# 130817_AriloRX_0_0.net
KiCad netlist of a schematic drawn in EAGLE
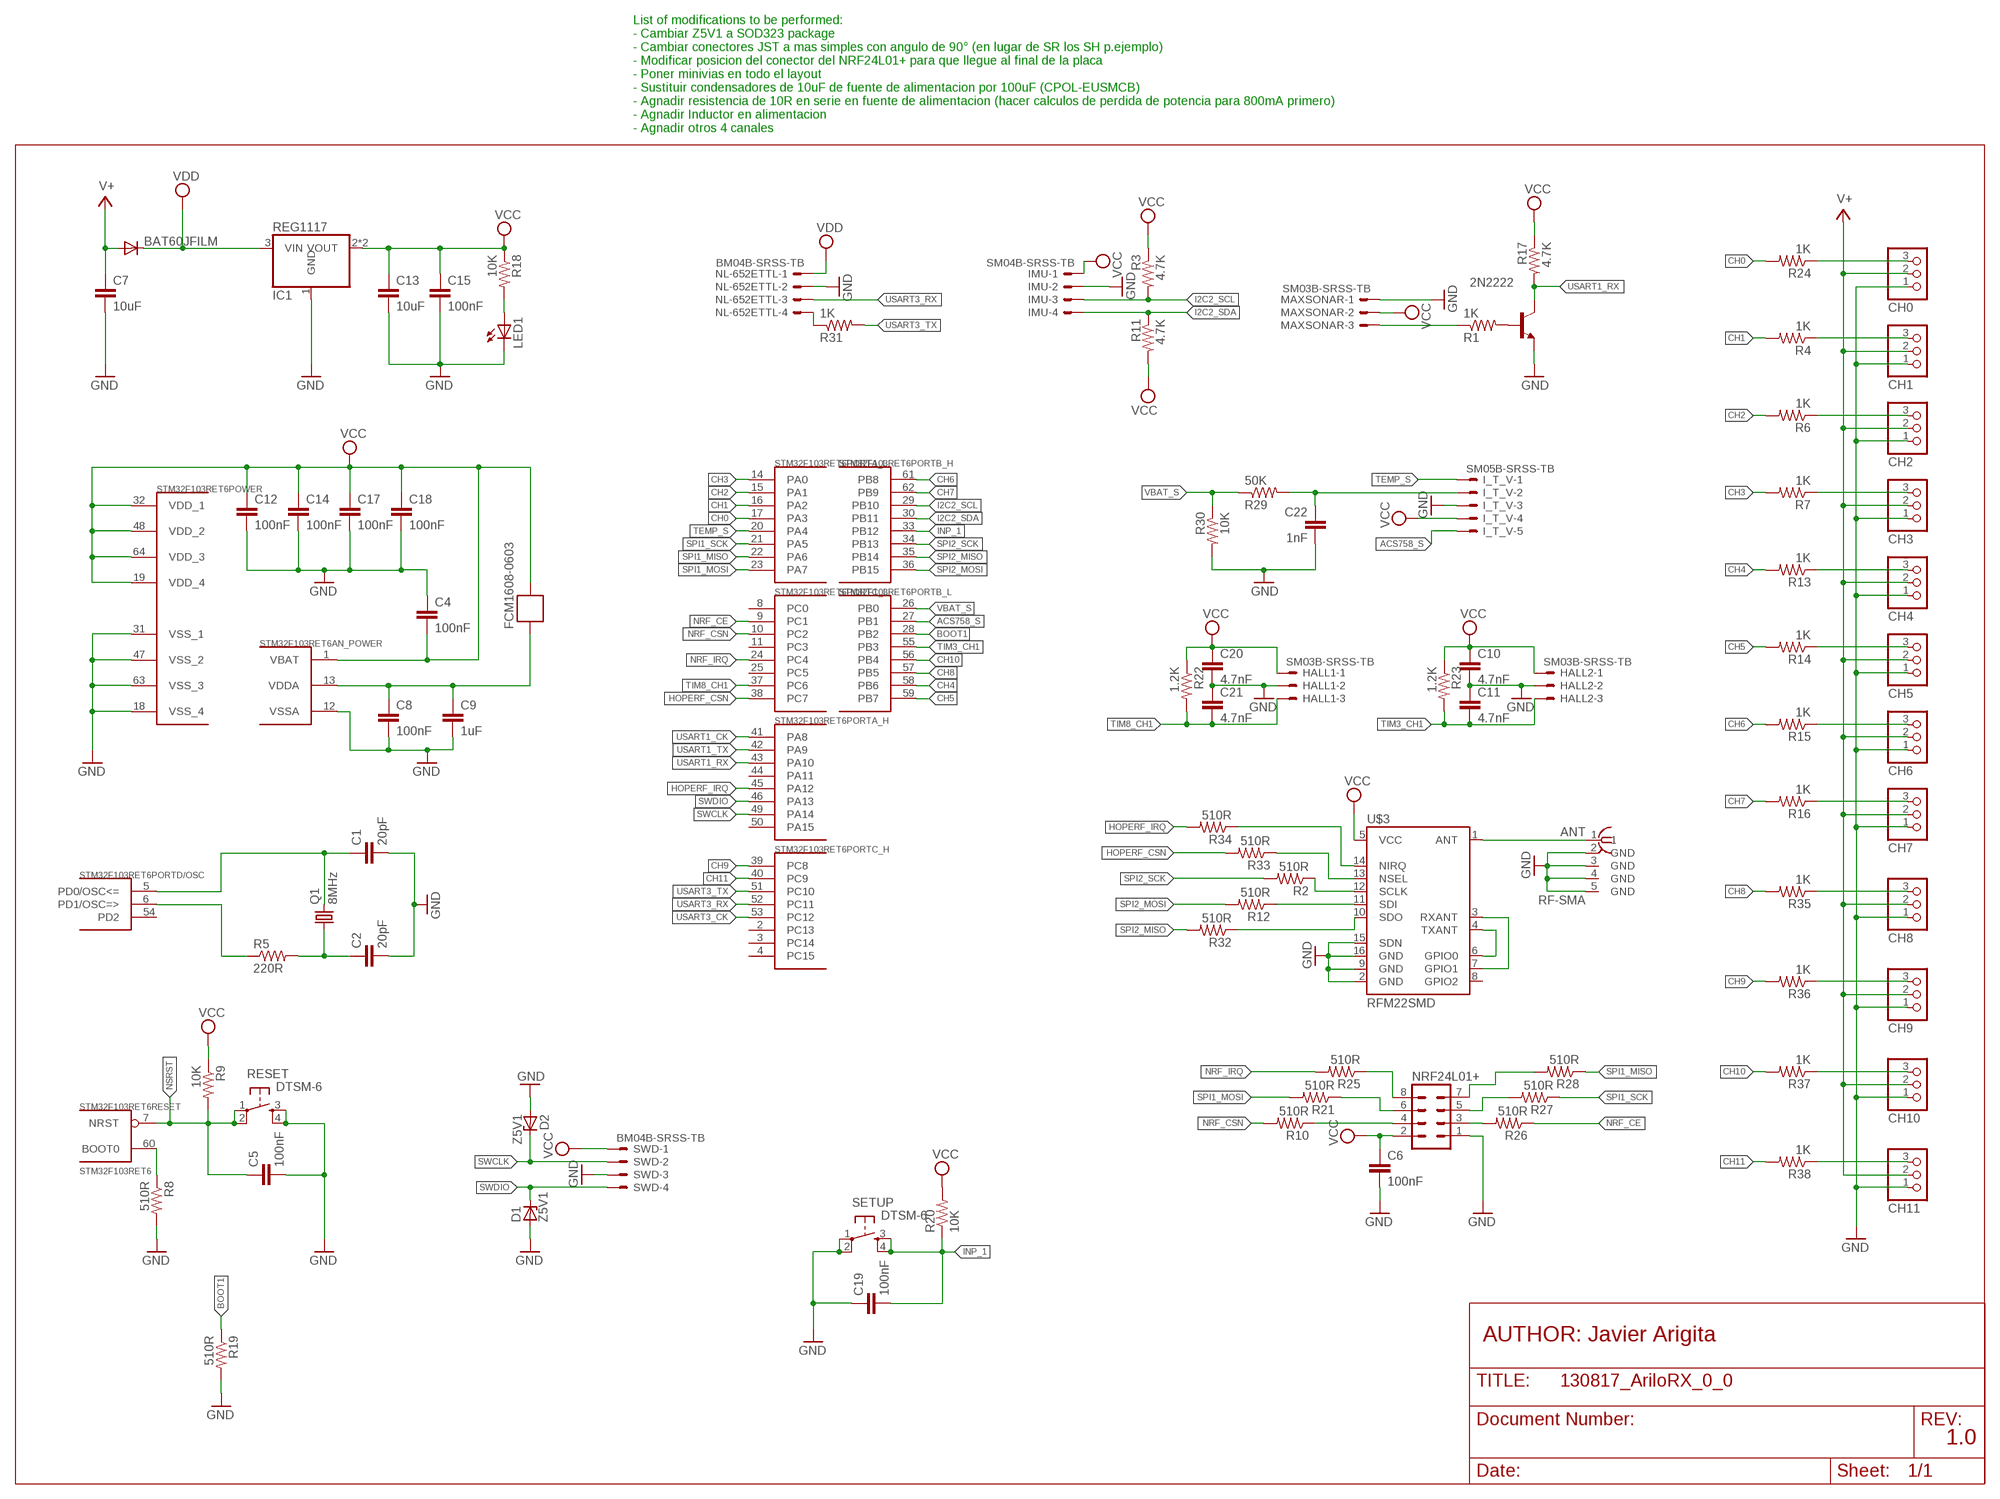
[diagram p0: schematic, sheet 1]

(export (version "E")
  (design (tool "Eeschema 10.0.6"))
  (components
    (comp (ref "2N2222")
      (value "MMBT2222ALT1-NPN-SOT23-BEC")
      (footprint "eagle-import:SOT23-BEC")
      (libsource (lib "eagle-import") (part "-NPN-SOT23-BECMMBT2222ALT1"))
    )
    (comp (ref "ANT")
      (value "RF-SMA")
      (footprint "eagle-import:BU-SMA-H")
      (libsource (lib "eagle-import") (part "RF-SMA"))
    )
    (comp (ref "BAT60JFILM")
      (value "DIODE-SOD323-R")
      (footprint "eagle-import:SOD323-R")
      (libsource (lib "eagle-import") (part "DIODE-SOD323-R"))
    )
    (comp (ref "C1")
      (value "20pF")
      (footprint "eagle-import:C0805")
      (libsource (lib "eagle-import") (part "C-EUC0805"))
    )
    (comp (ref "C2")
      (value "20pF")
      (footprint "eagle-import:C0805")
      (libsource (lib "eagle-import") (part "C-EUC0805"))
    )
    (comp (ref "C4")
      (value "100nF")
      (footprint "eagle-import:C0805")
      (libsource (lib "eagle-import") (part "C-EUC0805"))
    )
    (comp (ref "C5")
      (value "100nF")
      (footprint "eagle-import:C0805")
      (libsource (lib "eagle-import") (part "C-EUC0805"))
    )
    (comp (ref "C6")
      (value "100nF")
      (footprint "eagle-import:C0805")
      (libsource (lib "eagle-import") (part "C-EUC0805"))
    )
    (comp (ref "C7")
      (value "10uF")
      (footprint "eagle-import:C3216")
      (libsource (lib "eagle-import") (part "resistor_C-EUC3216"))
    )
    (comp (ref "C8")
      (value "100nF")
      (footprint "eagle-import:C0805")
      (libsource (lib "eagle-import") (part "C-EUC0805"))
    )
    (comp (ref "C9")
      (value "1uF")
      (footprint "eagle-import:C3216")
      (libsource (lib "eagle-import") (part "resistor_C-EUC3216"))
    )
    (comp (ref "C10")
      (value "4.7nF")
      (footprint "eagle-import:C0805")
      (libsource (lib "eagle-import") (part "C-EUC0805"))
    )
    (comp (ref "C11")
      (value "4.7nF")
      (footprint "eagle-import:C0805")
      (libsource (lib "eagle-import") (part "C-EUC0805"))
    )
    (comp (ref "C12")
      (value "100nF")
      (footprint "eagle-import:C0805")
      (libsource (lib "eagle-import") (part "C-EUC0805"))
    )
    (comp (ref "C13")
      (value "10uF")
      (footprint "eagle-import:C3216")
      (libsource (lib "eagle-import") (part "resistor_C-EUC3216"))
    )
    (comp (ref "C14")
      (value "100nF")
      (footprint "eagle-import:C0805")
      (libsource (lib "eagle-import") (part "C-EUC0805"))
    )
    (comp (ref "C15")
      (value "100nF")
      (footprint "eagle-import:C0805")
      (libsource (lib "eagle-import") (part "C-EUC0805"))
    )
    (comp (ref "C17")
      (value "100nF")
      (footprint "eagle-import:C0805")
      (libsource (lib "eagle-import") (part "C-EUC0805"))
    )
    (comp (ref "C18")
      (value "100nF")
      (footprint "eagle-import:C0805")
      (libsource (lib "eagle-import") (part "C-EUC0805"))
    )
    (comp (ref "C19")
      (value "100nF")
      (footprint "eagle-import:C0805")
      (libsource (lib "eagle-import") (part "C-EUC0805"))
    )
    (comp (ref "C20")
      (value "4.7nF")
      (footprint "eagle-import:C0805")
      (libsource (lib "eagle-import") (part "C-EUC0805"))
    )
    (comp (ref "C21")
      (value "4.7nF")
      (footprint "eagle-import:C0805")
      (libsource (lib "eagle-import") (part "C-EUC0805"))
    )
    (comp (ref "C22")
      (value "1nF")
      (footprint "eagle-import:C0805")
      (libsource (lib "eagle-import") (part "C-EUC0805"))
    )
    (comp (ref "CH0")
      (value "PINHD-1X3")
      (footprint "eagle-import:1X03")
      (libsource (lib "eagle-import") (part "PINHD-1X3"))
    )
    (comp (ref "CH1")
      (value "PINHD-1X3")
      (footprint "eagle-import:1X03")
      (libsource (lib "eagle-import") (part "PINHD-1X3"))
    )
    (comp (ref "CH2")
      (value "PINHD-1X3")
      (footprint "eagle-import:1X03")
      (libsource (lib "eagle-import") (part "PINHD-1X3"))
    )
    (comp (ref "CH3")
      (value "PINHD-1X3")
      (footprint "eagle-import:1X03")
      (libsource (lib "eagle-import") (part "PINHD-1X3"))
    )
    (comp (ref "CH4")
      (value "PINHD-1X3")
      (footprint "eagle-import:1X03")
      (libsource (lib "eagle-import") (part "PINHD-1X3"))
    )
    (comp (ref "CH5")
      (value "PINHD-1X3")
      (footprint "eagle-import:1X03")
      (libsource (lib "eagle-import") (part "PINHD-1X3"))
    )
    (comp (ref "CH6")
      (value "PINHD-1X3")
      (footprint "eagle-import:1X03")
      (libsource (lib "eagle-import") (part "PINHD-1X3"))
    )
    (comp (ref "CH7")
      (value "PINHD-1X3")
      (footprint "eagle-import:1X03")
      (libsource (lib "eagle-import") (part "PINHD-1X3"))
    )
    (comp (ref "CH8")
      (value "PINHD-1X3")
      (footprint "eagle-import:1X03")
      (libsource (lib "eagle-import") (part "PINHD-1X3"))
    )
    (comp (ref "CH9")
      (value "PINHD-1X3")
      (footprint "eagle-import:1X03")
      (libsource (lib "eagle-import") (part "PINHD-1X3"))
    )
    (comp (ref "CH10")
      (value "PINHD-1X3")
      (footprint "eagle-import:1X03")
      (libsource (lib "eagle-import") (part "PINHD-1X3"))
    )
    (comp (ref "CH11")
      (value "PINHD-1X3")
      (footprint "eagle-import:1X03")
      (libsource (lib "eagle-import") (part "PINHD-1X3"))
    )
    (comp (ref "D1")
      (value "Z5V1")
      (footprint "eagle-import:SOD80C")
      (libsource (lib "eagle-import") (part "ZENER-DIODESOD80C"))
    )
    (comp (ref "D2")
      (value "Z5V1")
      (footprint "eagle-import:SOD80C")
      (libsource (lib "eagle-import") (part "ZENER-DIODESOD80C"))
    )
    (comp (ref "FCM1608-0603")
      (value "FERRITE-BEAD")
      (footprint "eagle-import:R0603")
      (libsource (lib "eagle-import") (part "FERRITE-BEAD"))
    )
    (comp (ref "HALL1")
      (value "SM03B-SRSS-TB")
      (footprint "eagle-import:SM03B-SRSS-TB")
      (libsource (lib "eagle-import") (part "?M03B-SRSS-TBS"))
    )
    (comp (ref "HALL2")
      (value "SM03B-SRSS-TB")
      (footprint "eagle-import:SM03B-SRSS-TB")
      (libsource (lib "eagle-import") (part "?M03B-SRSS-TBS"))
    )
    (comp (ref "IC1")
      (value "REG1117")
      (footprint "eagle-import:SOT223")
      (libsource (lib "eagle-import") (part "REG1117"))
    )
    (comp (ref "IMU")
      (value "SM04B-SRSS-TB")
      (footprint "eagle-import:SM04B-SRSS-TB")
      (libsource (lib "eagle-import") (part "?M04B-SRSS-TBS"))
    )
    (comp (ref "I_T_V")
      (value "SM05B-SRSS-TB")
      (footprint "eagle-import:SM05B-SRSS-TB")
      (libsource (lib "eagle-import") (part "?M05B-SRSS-TBS"))
    )
    (comp (ref "LED1")
      (value "LED0805")
      (footprint "eagle-import:CHIPLED_0805")
      (libsource (lib "eagle-import") (part "LED0805"))
    )
    (comp (ref "MAXSONAR")
      (value "SM03B-SRSS-TB")
      (footprint "eagle-import:SM03B-SRSS-TB")
      (libsource (lib "eagle-import") (part "?M03B-SRSS-TBS"))
    )
    (comp (ref "NL-652ETTL")
      (value "BM04B-SRSS-TB")
      (footprint "eagle-import:BM04B-SRSS-TB")
      (libsource (lib "eagle-import") (part "?M04B-SRSS-TBB"))
    )
    (comp (ref "NRF24L01+")
      (value "MA04-2")
      (footprint "eagle-import:MA04-2")
      (libsource (lib "eagle-import") (part "MA04-2"))
    )
    (comp (ref "Q1")
      (value "8MHz")
      (footprint "eagle-import:SM49")
      (libsource (lib "eagle-import") (part "CRYSTALSM49"))
    )
    (comp (ref "R1")
      (value "1K")
      (footprint "eagle-import:R0805")
      (libsource (lib "eagle-import") (part "RESISTOR0805"))
    )
    (comp (ref "R2")
      (value "510R")
      (footprint "eagle-import:R0805")
      (libsource (lib "eagle-import") (part "RESISTOR0805"))
    )
    (comp (ref "R3")
      (value "4.7K")
      (footprint "eagle-import:R0805")
      (libsource (lib "eagle-import") (part "RESISTOR0805"))
    )
    (comp (ref "R4")
      (value "1K")
      (footprint "eagle-import:R0805")
      (libsource (lib "eagle-import") (part "RESISTOR0805"))
    )
    (comp (ref "R5")
      (value "220R")
      (footprint "eagle-import:R0805")
      (libsource (lib "eagle-import") (part "RESISTOR0805"))
    )
    (comp (ref "R6")
      (value "1K")
      (footprint "eagle-import:R0805")
      (libsource (lib "eagle-import") (part "RESISTOR0805"))
    )
    (comp (ref "R7")
      (value "1K")
      (footprint "eagle-import:R0805")
      (libsource (lib "eagle-import") (part "RESISTOR0805"))
    )
    (comp (ref "R8")
      (value "510R")
      (footprint "eagle-import:R0805")
      (libsource (lib "eagle-import") (part "RESISTOR0805"))
    )
    (comp (ref "R9")
      (value "10K")
      (footprint "eagle-import:R0805")
      (libsource (lib "eagle-import") (part "RESISTOR0805"))
    )
    (comp (ref "R10")
      (value "510R")
      (footprint "eagle-import:R0805")
      (libsource (lib "eagle-import") (part "RESISTOR0805"))
    )
    (comp (ref "R11")
      (value "4.7K")
      (footprint "eagle-import:R0805")
      (libsource (lib "eagle-import") (part "RESISTOR0805"))
    )
    (comp (ref "R12")
      (value "510R")
      (footprint "eagle-import:R0805")
      (libsource (lib "eagle-import") (part "RESISTOR0805"))
    )
    (comp (ref "R13")
      (value "1K")
      (footprint "eagle-import:R0805")
      (libsource (lib "eagle-import") (part "RESISTOR0805"))
    )
    (comp (ref "R14")
      (value "1K")
      (footprint "eagle-import:R0805")
      (libsource (lib "eagle-import") (part "RESISTOR0805"))
    )
    (comp (ref "R15")
      (value "1K")
      (footprint "eagle-import:R0805")
      (libsource (lib "eagle-import") (part "RESISTOR0805"))
    )
    (comp (ref "R16")
      (value "1K")
      (footprint "eagle-import:R0805")
      (libsource (lib "eagle-import") (part "RESISTOR0805"))
    )
    (comp (ref "R17")
      (value "4.7K")
      (footprint "eagle-import:R0805")
      (libsource (lib "eagle-import") (part "RESISTOR0805"))
    )
    (comp (ref "R18")
      (value "10K")
      (footprint "eagle-import:R0805")
      (libsource (lib "eagle-import") (part "RESISTOR0805"))
    )
    (comp (ref "R19")
      (value "510R")
      (footprint "eagle-import:R0805")
      (libsource (lib "eagle-import") (part "RESISTOR0805"))
    )
    (comp (ref "R20")
      (value "10K")
      (footprint "eagle-import:R0805")
      (libsource (lib "eagle-import") (part "RESISTOR0805"))
    )
    (comp (ref "R21")
      (value "510R")
      (footprint "eagle-import:R0805")
      (libsource (lib "eagle-import") (part "RESISTOR0805"))
    )
    (comp (ref "R22")
      (value "1.2K")
      (footprint "eagle-import:R0805")
      (libsource (lib "eagle-import") (part "RESISTOR0805"))
    )
    (comp (ref "R23")
      (value "1.2K")
      (footprint "eagle-import:R0805")
      (libsource (lib "eagle-import") (part "RESISTOR0805"))
    )
    (comp (ref "R24")
      (value "1K")
      (footprint "eagle-import:R0805")
      (libsource (lib "eagle-import") (part "RESISTOR0805"))
    )
    (comp (ref "R25")
      (value "510R")
      (footprint "eagle-import:R0805")
      (libsource (lib "eagle-import") (part "RESISTOR0805"))
    )
    (comp (ref "R26")
      (value "510R")
      (footprint "eagle-import:R0805")
      (libsource (lib "eagle-import") (part "RESISTOR0805"))
    )
    (comp (ref "R27")
      (value "510R")
      (footprint "eagle-import:R0805")
      (libsource (lib "eagle-import") (part "RESISTOR0805"))
    )
    (comp (ref "R28")
      (value "510R")
      (footprint "eagle-import:R0805")
      (libsource (lib "eagle-import") (part "RESISTOR0805"))
    )
    (comp (ref "R29")
      (value "50K")
      (footprint "eagle-import:R0805")
      (libsource (lib "eagle-import") (part "RESISTOR0805"))
    )
    (comp (ref "R30")
      (value "10K")
      (footprint "eagle-import:R0805")
      (libsource (lib "eagle-import") (part "RESISTOR0805"))
    )
    (comp (ref "R31")
      (value "1K")
      (footprint "eagle-import:R0805")
      (libsource (lib "eagle-import") (part "RESISTOR0805"))
    )
    (comp (ref "R32")
      (value "510R")
      (footprint "eagle-import:R0805")
      (libsource (lib "eagle-import") (part "RESISTOR0805"))
    )
    (comp (ref "R33")
      (value "510R")
      (footprint "eagle-import:R0805")
      (libsource (lib "eagle-import") (part "RESISTOR0805"))
    )
    (comp (ref "R34")
      (value "510R")
      (footprint "eagle-import:R0805")
      (libsource (lib "eagle-import") (part "RESISTOR0805"))
    )
    (comp (ref "R35")
      (value "1K")
      (footprint "eagle-import:R0805")
      (libsource (lib "eagle-import") (part "RESISTOR0805"))
    )
    (comp (ref "R36")
      (value "1K")
      (footprint "eagle-import:R0805")
      (libsource (lib "eagle-import") (part "RESISTOR0805"))
    )
    (comp (ref "R37")
      (value "1K")
      (footprint "eagle-import:R0805")
      (libsource (lib "eagle-import") (part "RESISTOR0805"))
    )
    (comp (ref "R38")
      (value "1K")
      (footprint "eagle-import:R0805")
      (libsource (lib "eagle-import") (part "RESISTOR0805"))
    )
    (comp (ref "RESET")
      (value "DTSM-6")
      (footprint "eagle-import:DTSM-6")
      (libsource (lib "eagle-import") (part "DTSM-6"))
    )
    (comp (ref "SETUP")
      (value "DTSM-6")
      (footprint "eagle-import:DTSM-6")
      (libsource (lib "eagle-import") (part "DTSM-6"))
    )
    (comp (ref "STM32F103RET6")
      (value "STM32F103RET6")
      (footprint "eagle-import:TQFP64")
      (libsource (lib "eagle-import") (part "STM32F10XRXT6"))
    )
    (comp (ref "SWD")
      (value "BM04B-SRSS-TB")
      (footprint "eagle-import:BM04B-SRSS-TB")
      (libsource (lib "eagle-import") (part "?M04B-SRSS-TBB"))
    )
    (comp (ref "U$3")
      (value "RFM22SMD")
      (footprint "eagle-import:RFM22-XXX-S2")
      (libsource (lib "eagle-import") (part "RFM22SMD"))
    )
  )
  (nets
    (net (code "1") (name "ACS758_S") (class "Default")
      (node (ref "I_T_V") (pin "5") (pinfunction "S_5") (pintype "passive"))
      (node (ref "STM32F103RET6") (pin "27") (pinfunction "PB1_27") (pintype "bidirectional"))
    )
    (net (code "2") (name "BOOT1") (class "Default")
      (node (ref "R19") (pin "1") (pinfunction "1_1") (pintype "passive"))
      (node (ref "STM32F103RET6") (pin "28") (pinfunction "PB2_28") (pintype "bidirectional"))
    )
    (net (code "3") (name "CH0") (class "Default")
      (node (ref "R24") (pin "2") (pinfunction "2_2") (pintype "passive"))
      (node (ref "STM32F103RET6") (pin "17") (pinfunction "PA3_17") (pintype "bidirectional"))
    )
    (net (code "4") (name "CH1") (class "Default")
      (node (ref "R4") (pin "2") (pinfunction "2_2") (pintype "passive"))
      (node (ref "STM32F103RET6") (pin "16") (pinfunction "PA2_16") (pintype "bidirectional"))
    )
    (net (code "5") (name "CH2") (class "Default")
      (node (ref "R6") (pin "2") (pinfunction "2_2") (pintype "passive"))
      (node (ref "STM32F103RET6") (pin "15") (pinfunction "PA1_15") (pintype "bidirectional"))
    )
    (net (code "6") (name "CH3") (class "Default")
      (node (ref "R7") (pin "2") (pinfunction "2_2") (pintype "passive"))
      (node (ref "STM32F103RET6") (pin "14") (pinfunction "PA0_14") (pintype "bidirectional"))
    )
    (net (code "7") (name "CH4") (class "Default")
      (node (ref "R13") (pin "2") (pinfunction "2_2") (pintype "passive"))
      (node (ref "STM32F103RET6") (pin "58") (pinfunction "PB6_58") (pintype "bidirectional"))
    )
    (net (code "8") (name "CH5") (class "Default")
      (node (ref "R14") (pin "2") (pinfunction "2_2") (pintype "passive"))
      (node (ref "STM32F103RET6") (pin "59") (pinfunction "PB7_59") (pintype "bidirectional"))
    )
    (net (code "9") (name "CH6") (class "Default")
      (node (ref "R15") (pin "2") (pinfunction "2_2") (pintype "passive"))
      (node (ref "STM32F103RET6") (pin "61") (pinfunction "PB8_61") (pintype "bidirectional"))
    )
    (net (code "10") (name "CH7") (class "Default")
      (node (ref "R16") (pin "2") (pinfunction "2_2") (pintype "passive"))
      (node (ref "STM32F103RET6") (pin "62") (pinfunction "PB9_62") (pintype "bidirectional"))
    )
    (net (code "11") (name "CH8") (class "Default")
      (node (ref "R35") (pin "2") (pinfunction "2_2") (pintype "passive"))
      (node (ref "STM32F103RET6") (pin "57") (pinfunction "PB5_57") (pintype "bidirectional"))
    )
    (net (code "12") (name "CH9") (class "Default")
      (node (ref "R36") (pin "2") (pinfunction "2_2") (pintype "passive"))
      (node (ref "STM32F103RET6") (pin "39") (pinfunction "PC8_39") (pintype "bidirectional"))
    )
    (net (code "13") (name "CH10") (class "Default")
      (node (ref "R37") (pin "2") (pinfunction "2_2") (pintype "passive"))
      (node (ref "STM32F103RET6") (pin "56") (pinfunction "PB4_56") (pintype "bidirectional"))
    )
    (net (code "14") (name "CH11") (class "Default")
      (node (ref "R38") (pin "2") (pinfunction "2_2") (pintype "passive"))
      (node (ref "STM32F103RET6") (pin "40") (pinfunction "PC9_40") (pintype "bidirectional"))
    )
    (net (code "15") (name "GND") (class "Default")
      (node (ref "2N2222") (pin "E") (pinfunction "E_E") (pintype "passive"))
      (node (ref "ANT") (pin "2") (pinfunction "GND_2") (pintype "power_in"))
      (node (ref "ANT") (pin "3") (pinfunction "GND_3") (pintype "bidirectional"))
      (node (ref "ANT") (pin "4") (pinfunction "GND_4") (pintype "bidirectional"))
      (node (ref "ANT") (pin "5") (pinfunction "GND_5") (pintype "bidirectional"))
      (node (ref "C1") (pin "2") (pinfunction "2_2") (pintype "passive"))
      (node (ref "C10") (pin "2") (pinfunction "2_2") (pintype "passive"))
      (node (ref "C11") (pin "1") (pinfunction "1_1") (pintype "passive"))
      (node (ref "C12") (pin "2") (pinfunction "2_2") (pintype "passive"))
      (node (ref "C13") (pin "2") (pinfunction "2_2") (pintype "passive"))
      (node (ref "C14") (pin "2") (pinfunction "2_2") (pintype "passive"))
      (node (ref "C15") (pin "2") (pinfunction "2_2") (pintype "passive"))
      (node (ref "C17") (pin "2") (pinfunction "2_2") (pintype "passive"))
      (node (ref "C18") (pin "2") (pinfunction "2_2") (pintype "passive"))
      (node (ref "C19") (pin "1") (pinfunction "1_1") (pintype "passive"))
      (node (ref "C2") (pin "2") (pinfunction "2_2") (pintype "passive"))
      (node (ref "C20") (pin "2") (pinfunction "2_2") (pintype "passive"))
      (node (ref "C21") (pin "1") (pinfunction "1_1") (pintype "passive"))
      (node (ref "C22") (pin "2") (pinfunction "2_2") (pintype "passive"))
      (node (ref "C4") (pin "1") (pinfunction "1_1") (pintype "passive"))
      (node (ref "C5") (pin "2") (pinfunction "2_2") (pintype "passive"))
      (node (ref "C6") (pin "2") (pinfunction "2_2") (pintype "passive"))
      (node (ref "C7") (pin "2") (pinfunction "2_2") (pintype "passive"))
      (node (ref "C8") (pin "2") (pinfunction "2_2") (pintype "passive"))
      (node (ref "C9") (pin "2") (pinfunction "2_2") (pintype "passive"))
      (node (ref "CH0") (pin "1") (pinfunction "1_1") (pintype "passive"))
      (node (ref "CH1") (pin "1") (pinfunction "1_1") (pintype "passive"))
      (node (ref "CH10") (pin "1") (pinfunction "1_1") (pintype "passive"))
      (node (ref "CH11") (pin "1") (pinfunction "1_1") (pintype "passive"))
      (node (ref "CH2") (pin "1") (pinfunction "1_1") (pintype "passive"))
      (node (ref "CH3") (pin "1") (pinfunction "1_1") (pintype "passive"))
      (node (ref "CH4") (pin "1") (pinfunction "1_1") (pintype "passive"))
      (node (ref "CH5") (pin "1") (pinfunction "1_1") (pintype "passive"))
      (node (ref "CH6") (pin "1") (pinfunction "1_1") (pintype "passive"))
      (node (ref "CH7") (pin "1") (pinfunction "1_1") (pintype "passive"))
      (node (ref "CH8") (pin "1") (pinfunction "1_1") (pintype "passive"))
      (node (ref "CH9") (pin "1") (pinfunction "1_1") (pintype "passive"))
      (node (ref "D1") (pin "A") (pinfunction "A_A") (pintype "passive"))
      (node (ref "D2") (pin "A") (pinfunction "A_A") (pintype "passive"))
      (node (ref "HALL1") (pin "2") (pinfunction "S_2") (pintype "passive"))
      (node (ref "HALL2") (pin "2") (pinfunction "S_2") (pintype "passive"))
      (node (ref "IC1") (pin "1") (pinfunction "GND_1") (pintype "power_in"))
      (node (ref "IMU") (pin "2") (pinfunction "S_2") (pintype "passive"))
      (node (ref "I_T_V") (pin "3") (pinfunction "S_3") (pintype "passive"))
      (node (ref "LED1") (pin "C") (pinfunction "C_C") (pintype "passive"))
      (node (ref "MAXSONAR") (pin "1") (pinfunction "S_1") (pintype "passive"))
      (node (ref "NL-652ETTL") (pin "2") (pinfunction "S_2") (pintype "passive"))
      (node (ref "NRF24L01+") (pin "1") (pinfunction "1_1") (pintype "passive"))
      (node (ref "R19") (pin "2") (pinfunction "2_2") (pintype "passive"))
      (node (ref "R30") (pin "2") (pinfunction "2_2") (pintype "passive"))
      (node (ref "R8") (pin "2") (pinfunction "2_2") (pintype "passive"))
      (node (ref "RESET") (pin "3") (pinfunction "3_3") (pintype "passive"))
      (node (ref "RESET") (pin "4") (pinfunction "4_4") (pintype "passive"))
      (node (ref "SETUP") (pin "1") (pinfunction "1_1") (pintype "passive"))
      (node (ref "SETUP") (pin "2") (pinfunction "2_2") (pintype "passive"))
      (node (ref "STM32F103RET6") (pin "12") (pinfunction "VSSA_12") (pintype "power_in"))
      (node (ref "STM32F103RET6") (pin "18") (pinfunction "VSS_4_18") (pintype "power_in"))
      (node (ref "STM32F103RET6") (pin "31") (pinfunction "VSS_1_31") (pintype "power_in"))
      (node (ref "STM32F103RET6") (pin "47") (pinfunction "VSS_2_47") (pintype "power_in"))
      (node (ref "STM32F103RET6") (pin "63") (pinfunction "VSS_3_63") (pintype "power_in"))
      (node (ref "SWD") (pin "3") (pinfunction "S_3") (pintype "passive"))
      (node (ref "U$3") (pin "15") (pinfunction "SDN_15") (pintype "input"))
      (node (ref "U$3") (pin "16") (pinfunction "GND_16") (pintype "power_in"))
      (node (ref "U$3") (pin "2") (pinfunction "GND_2") (pintype "power_in"))
      (node (ref "U$3") (pin "9") (pinfunction "GND_9") (pintype "power_in"))
    )
    (net (code "16") (name "HOPERF_CSN") (class "Default")
      (node (ref "R33") (pin "2") (pinfunction "2_2") (pintype "passive"))
      (node (ref "STM32F103RET6") (pin "38") (pinfunction "PC7_38") (pintype "bidirectional"))
    )
    (net (code "17") (name "HOPERF_IRQ") (class "Default")
      (node (ref "R34") (pin "2") (pinfunction "2_2") (pintype "passive"))
      (node (ref "STM32F103RET6") (pin "45") (pinfunction "PA12_45") (pintype "bidirectional"))
    )
    (net (code "18") (name "I2C2_SCL") (class "Default")
      (node (ref "IMU") (pin "3") (pinfunction "S_3") (pintype "passive"))
      (node (ref "R3") (pin "2") (pinfunction "2_2") (pintype "passive"))
      (node (ref "STM32F103RET6") (pin "29") (pinfunction "PB10_29") (pintype "bidirectional"))
    )
    (net (code "19") (name "I2C2_SDA") (class "Default")
      (node (ref "IMU") (pin "4") (pinfunction "S_4") (pintype "passive"))
      (node (ref "R11") (pin "1") (pinfunction "1_1") (pintype "passive"))
      (node (ref "STM32F103RET6") (pin "30") (pinfunction "PB11_30") (pintype "bidirectional"))
    )
    (net (code "20") (name "INP_1") (class "Default")
      (node (ref "C19") (pin "2") (pinfunction "2_2") (pintype "passive"))
      (node (ref "R20") (pin "1") (pinfunction "1_1") (pintype "passive"))
      (node (ref "SETUP") (pin "3") (pinfunction "3_3") (pintype "passive"))
      (node (ref "SETUP") (pin "4") (pinfunction "4_4") (pintype "passive"))
      (node (ref "STM32F103RET6") (pin "33") (pinfunction "PB12_33") (pintype "bidirectional"))
    )
    (net (code "21") (name "NRF_CE") (class "Default")
      (node (ref "R26") (pin "1") (pinfunction "1_1") (pintype "passive"))
      (node (ref "STM32F103RET6") (pin "9") (pinfunction "PC1_9") (pintype "bidirectional"))
    )
    (net (code "22") (name "NRF_CSN") (class "Default")
      (node (ref "R10") (pin "2") (pinfunction "2_2") (pintype "passive"))
      (node (ref "STM32F103RET6") (pin "10") (pinfunction "PC2_10") (pintype "bidirectional"))
    )
    (net (code "23") (name "NRF_IRQ") (class "Default")
      (node (ref "R25") (pin "2") (pinfunction "2_2") (pintype "passive"))
      (node (ref "STM32F103RET6") (pin "24") (pinfunction "PC4_24") (pintype "bidirectional"))
    )
    (net (code "24") (name "NSRST") (class "Default")
      (node (ref "C5") (pin "1") (pinfunction "1_1") (pintype "passive"))
      (node (ref "R9") (pin "2") (pinfunction "2_2") (pintype "passive"))
      (node (ref "RESET") (pin "1") (pinfunction "1_1") (pintype "passive"))
      (node (ref "RESET") (pin "2") (pinfunction "2_2") (pintype "passive"))
      (node (ref "STM32F103RET6") (pin "7") (pinfunction "NRST_7") (pintype "input"))
    )
    (net (code "25") (name "Net-(2N2222-PadB)") (class "Default")
      (node (ref "2N2222") (pin "B") (pinfunction "B_B") (pintype "passive"))
      (node (ref "R1") (pin "2") (pinfunction "2_2") (pintype "passive"))
    )
    (net (code "26") (name "Net-(C2-Pad1)") (class "Default")
      (node (ref "C2") (pin "1") (pinfunction "1_1") (pintype "passive"))
      (node (ref "Q1") (pin "1") (pinfunction "1_1") (pintype "passive"))
      (node (ref "R5") (pin "2") (pinfunction "2_2") (pintype "passive"))
    )
    (net (code "27") (name "Net-(CH0-Pad3)") (class "Default")
      (node (ref "CH0") (pin "3") (pinfunction "3_3") (pintype "passive"))
      (node (ref "R24") (pin "1") (pinfunction "1_1") (pintype "passive"))
    )
    (net (code "28") (name "Net-(CH1-Pad3)") (class "Default")
      (node (ref "CH1") (pin "3") (pinfunction "3_3") (pintype "passive"))
      (node (ref "R4") (pin "1") (pinfunction "1_1") (pintype "passive"))
    )
    (net (code "29") (name "Net-(CH2-Pad3)") (class "Default")
      (node (ref "CH2") (pin "3") (pinfunction "3_3") (pintype "passive"))
      (node (ref "R6") (pin "1") (pinfunction "1_1") (pintype "passive"))
    )
    (net (code "30") (name "Net-(CH3-Pad3)") (class "Default")
      (node (ref "CH3") (pin "3") (pinfunction "3_3") (pintype "passive"))
      (node (ref "R7") (pin "1") (pinfunction "1_1") (pintype "passive"))
    )
    (net (code "31") (name "Net-(CH4-Pad3)") (class "Default")
      (node (ref "CH4") (pin "3") (pinfunction "3_3") (pintype "passive"))
      (node (ref "R13") (pin "1") (pinfunction "1_1") (pintype "passive"))
    )
    (net (code "32") (name "Net-(CH5-Pad3)") (class "Default")
      (node (ref "CH5") (pin "3") (pinfunction "3_3") (pintype "passive"))
      (node (ref "R14") (pin "1") (pinfunction "1_1") (pintype "passive"))
    )
    (net (code "33") (name "Net-(CH6-Pad3)") (class "Default")
      (node (ref "CH6") (pin "3") (pinfunction "3_3") (pintype "passive"))
      (node (ref "R15") (pin "1") (pinfunction "1_1") (pintype "passive"))
    )
    (net (code "34") (name "Net-(CH7-Pad3)") (class "Default")
      (node (ref "CH7") (pin "3") (pinfunction "3_3") (pintype "passive"))
      (node (ref "R16") (pin "1") (pinfunction "1_1") (pintype "passive"))
    )
    (net (code "35") (name "Net-(CH8-Pad3)") (class "Default")
      (node (ref "CH8") (pin "3") (pinfunction "3_3") (pintype "passive"))
      (node (ref "R35") (pin "1") (pinfunction "1_1") (pintype "passive"))
    )
    (net (code "36") (name "Net-(CH9-Pad3)") (class "Default")
      (node (ref "CH9") (pin "3") (pinfunction "3_3") (pintype "passive"))
      (node (ref "R36") (pin "1") (pinfunction "1_1") (pintype "passive"))
    )
    (net (code "37") (name "Net-(CH10-Pad3)") (class "Default")
      (node (ref "CH10") (pin "3") (pinfunction "3_3") (pintype "passive"))
      (node (ref "R37") (pin "1") (pinfunction "1_1") (pintype "passive"))
    )
    (net (code "38") (name "Net-(CH11-Pad3)") (class "Default")
      (node (ref "CH11") (pin "3") (pinfunction "3_3") (pintype "passive"))
      (node (ref "R38") (pin "1") (pinfunction "1_1") (pintype "passive"))
    )
    (net (code "39") (name "Net-(FCM1608-0603-P$2)") (class "Default")
      (node (ref "C8") (pin "1") (pinfunction "1_1") (pintype "passive"))
      (node (ref "C9") (pin "1") (pinfunction "1_1") (pintype "passive"))
      (node (ref "FCM1608-0603") (pin "2") (pinfunction "P$2_2") (pintype "bidirectional"))
      (node (ref "STM32F103RET6") (pin "13") (pinfunction "VDDA_13") (pintype "power_in"))
    )
    (net (code "40") (name "Net-(I_T_VB-S)") (class "Default")
      (node (ref "C22") (pin "1") (pinfunction "1_1") (pintype "passive"))
      (node (ref "I_T_V") (pin "2") (pinfunction "S_2") (pintype "passive"))
      (node (ref "R29") (pin "2") (pinfunction "2_2") (pintype "passive"))
    )
    (net (code "41") (name "Net-(LED1-PadA)") (class "Default")
      (node (ref "LED1") (pin "A") (pinfunction "A_A") (pintype "passive"))
      (node (ref "R18") (pin "2") (pinfunction "2_2") (pintype "passive"))
    )
    (net (code "42") (name "Net-(MAXSONARC-S)") (class "Default")
      (node (ref "MAXSONAR") (pin "3") (pinfunction "S_3") (pintype "passive"))
      (node (ref "R1") (pin "1") (pinfunction "1_1") (pintype "passive"))
    )
    (net (code "43") (name "Net-(NL-652ETTLD-S)") (class "Default")
      (node (ref "NL-652ETTL") (pin "4") (pinfunction "S_4") (pintype "passive"))
      (node (ref "R31") (pin "1") (pinfunction "1_1") (pintype "passive"))
    )
    (net (code "44") (name "Net-(NRF24L01+-Pad3)") (class "Default")
      (node (ref "NRF24L01+") (pin "3") (pinfunction "3_3") (pintype "passive"))
      (node (ref "R26") (pin "2") (pinfunction "2_2") (pintype "passive"))
    )
    (net (code "45") (name "Net-(NRF24L01+-Pad4)") (class "Default")
      (node (ref "NRF24L01+") (pin "4") (pinfunction "4_4") (pintype "passive"))
      (node (ref "R10") (pin "1") (pinfunction "1_1") (pintype "passive"))
    )
    (net (code "46") (name "Net-(NRF24L01+-Pad5)") (class "Default")
      (node (ref "NRF24L01+") (pin "5") (pinfunction "5_5") (pintype "passive"))
      (node (ref "R27") (pin "2") (pinfunction "2_2") (pintype "passive"))
    )
    (net (code "47") (name "Net-(NRF24L01+-Pad6)") (class "Default")
      (node (ref "NRF24L01+") (pin "6") (pinfunction "6_6") (pintype "passive"))
      (node (ref "R21") (pin "1") (pinfunction "1_1") (pintype "passive"))
    )
    (net (code "48") (name "Net-(NRF24L01+-Pad7)") (class "Default")
      (node (ref "NRF24L01+") (pin "7") (pinfunction "7_7") (pintype "passive"))
      (node (ref "R28") (pin "2") (pinfunction "2_2") (pintype "passive"))
    )
    (net (code "49") (name "Net-(NRF24L01+-Pad8)") (class "Default")
      (node (ref "NRF24L01+") (pin "8") (pinfunction "8_8") (pintype "passive"))
      (node (ref "R25") (pin "1") (pinfunction "1_1") (pintype "passive"))
    )
    (net (code "50") (name "Net-(STM32F103RET6H-PD0{slash}OSC<=)") (class "Default")
      (node (ref "C1") (pin "1") (pinfunction "1_1") (pintype "passive"))
      (node (ref "Q1") (pin "2") (pinfunction "2_2") (pintype "passive"))
      (node (ref "STM32F103RET6") (pin "5") (pinfunction "PD0/OSC<=_5") (pintype "bidirectional"))
    )
    (net (code "51") (name "Net-(STM32F103RET6H-PD1{slash}OSC=>)") (class "Default")
      (node (ref "R5") (pin "1") (pinfunction "1_1") (pintype "passive"))
      (node (ref "STM32F103RET6") (pin "6") (pinfunction "PD1/OSC=>_6") (pintype "bidirectional"))
    )
    (net (code "52") (name "Net-(STM32F103RET6J-BOOT0)") (class "Default")
      (node (ref "R8") (pin "1") (pinfunction "1_1") (pintype "passive"))
      (node (ref "STM32F103RET6") (pin "60") (pinfunction "BOOT0_60") (pintype "input"))
    )
    (net (code "53") (name "Net-(U$3-ANT)") (class "Default")
      (node (ref "ANT") (pin "1") (pinfunction "1_1") (pintype "passive"))
      (node (ref "U$3") (pin "1") (pinfunction "ANT_1") (pintype "bidirectional"))
    )
    (net (code "54") (name "Net-(U$3-GPIO0)") (class "Default")
      (node (ref "U$3") (pin "4") (pinfunction "TXANT_4") (pintype "input"))
      (node (ref "U$3") (pin "6") (pinfunction "GPIO0_6") (pintype "bidirectional"))
    )
    (net (code "55") (name "Net-(U$3-GPIO1)") (class "Default")
      (node (ref "U$3") (pin "3") (pinfunction "RXANT_3") (pintype "input"))
      (node (ref "U$3") (pin "7") (pinfunction "GPIO1_7") (pintype "bidirectional"))
    )
    (net (code "56") (name "Net-(U$3-NIRQ)") (class "Default")
      (node (ref "R34") (pin "1") (pinfunction "1_1") (pintype "passive"))
      (node (ref "U$3") (pin "14") (pinfunction "NIRQ_14") (pintype "output"))
    )
    (net (code "57") (name "Net-(U$3-NSEL)") (class "Default")
      (node (ref "R33") (pin "1") (pinfunction "1_1") (pintype "passive"))
      (node (ref "U$3") (pin "13") (pinfunction "NSEL_13") (pintype "input"))
    )
    (net (code "58") (name "Net-(U$3-SCLK)") (class "Default")
      (node (ref "R2") (pin "1") (pinfunction "1_1") (pintype "passive"))
      (node (ref "U$3") (pin "12") (pinfunction "SCLK_12") (pintype "input"))
    )
    (net (code "59") (name "Net-(U$3-SDI)") (class "Default")
      (node (ref "R12") (pin "1") (pinfunction "1_1") (pintype "passive"))
      (node (ref "U$3") (pin "11") (pinfunction "SDI_11") (pintype "input"))
    )
    (net (code "60") (name "Net-(U$3-SDO)") (class "Default")
      (node (ref "R32") (pin "1") (pinfunction "1_1") (pintype "passive"))
      (node (ref "U$3") (pin "10") (pinfunction "SDO_10") (pintype "output"))
    )
    (net (code "61") (name "SPI1_MISO") (class "Default")
      (node (ref "R28") (pin "1") (pinfunction "1_1") (pintype "passive"))
      (node (ref "STM32F103RET6") (pin "22") (pinfunction "PA6_22") (pintype "bidirectional"))
    )
    (net (code "62") (name "SPI1_MOSI") (class "Default")
      (node (ref "R21") (pin "2") (pinfunction "2_2") (pintype "passive"))
      (node (ref "STM32F103RET6") (pin "23") (pinfunction "PA7_23") (pintype "bidirectional"))
    )
    (net (code "63") (name "SPI1_SCK") (class "Default")
      (node (ref "R27") (pin "1") (pinfunction "1_1") (pintype "passive"))
      (node (ref "STM32F103RET6") (pin "21") (pinfunction "PA5_21") (pintype "bidirectional"))
    )
    (net (code "64") (name "SPI2_MISO") (class "Default")
      (node (ref "R32") (pin "2") (pinfunction "2_2") (pintype "passive"))
      (node (ref "STM32F103RET6") (pin "35") (pinfunction "PB14_35") (pintype "bidirectional"))
    )
    (net (code "65") (name "SPI2_MOSI") (class "Default")
      (node (ref "R12") (pin "2") (pinfunction "2_2") (pintype "passive"))
      (node (ref "STM32F103RET6") (pin "36") (pinfunction "PB15_36") (pintype "bidirectional"))
    )
    (net (code "66") (name "SPI2_SCK") (class "Default")
      (node (ref "R2") (pin "2") (pinfunction "2_2") (pintype "passive"))
      (node (ref "STM32F103RET6") (pin "34") (pinfunction "PB13_34") (pintype "bidirectional"))
    )
    (net (code "67") (name "SWCLK") (class "Default")
      (node (ref "D2") (pin "C") (pinfunction "C_C") (pintype "passive"))
      (node (ref "STM32F103RET6") (pin "49") (pinfunction "PA14_49") (pintype "bidirectional"))
      (node (ref "SWD") (pin "2") (pinfunction "S_2") (pintype "passive"))
    )
    (net (code "68") (name "SWDIO") (class "Default")
      (node (ref "D1") (pin "C") (pinfunction "C_C") (pintype "passive"))
      (node (ref "STM32F103RET6") (pin "46") (pinfunction "PA13_46") (pintype "bidirectional"))
      (node (ref "SWD") (pin "4") (pinfunction "S_4") (pintype "passive"))
    )
    (net (code "69") (name "TEMP_S") (class "Default")
      (node (ref "I_T_V") (pin "1") (pinfunction "S_1") (pintype "passive"))
      (node (ref "STM32F103RET6") (pin "20") (pinfunction "PA4_20") (pintype "bidirectional"))
    )
    (net (code "70") (name "TIM3_CH1") (class "Default")
      (node (ref "C11") (pin "2") (pinfunction "2_2") (pintype "passive"))
      (node (ref "HALL2") (pin "3") (pinfunction "S_3") (pintype "passive"))
      (node (ref "R23") (pin "2") (pinfunction "2_2") (pintype "passive"))
      (node (ref "STM32F103RET6") (pin "55") (pinfunction "PB3_55") (pintype "bidirectional"))
    )
    (net (code "71") (name "TIM8_CH1") (class "Default")
      (node (ref "C21") (pin "2") (pinfunction "2_2") (pintype "passive"))
      (node (ref "HALL1") (pin "3") (pinfunction "S_3") (pintype "passive"))
      (node (ref "R22") (pin "2") (pinfunction "2_2") (pintype "passive"))
      (node (ref "STM32F103RET6") (pin "37") (pinfunction "PC6_37") (pintype "bidirectional"))
    )
    (net (code "72") (name "USART1_CK") (class "Default")
      (node (ref "STM32F103RET6") (pin "41") (pinfunction "PA8_41") (pintype "bidirectional"))
    )
    (net (code "73") (name "USART1_RX") (class "Default")
      (node (ref "2N2222") (pin "C") (pinfunction "C_C") (pintype "passive"))
      (node (ref "R17") (pin "2") (pinfunction "2_2") (pintype "passive"))
      (node (ref "STM32F103RET6") (pin "43") (pinfunction "PA10_43") (pintype "bidirectional"))
    )
    (net (code "74") (name "USART1_TX") (class "Default")
      (node (ref "STM32F103RET6") (pin "42") (pinfunction "PA9_42") (pintype "bidirectional"))
    )
    (net (code "75") (name "USART3_CK") (class "Default")
      (node (ref "STM32F103RET6") (pin "53") (pinfunction "PC12_53") (pintype "bidirectional"))
    )
    (net (code "76") (name "USART3_RX") (class "Default")
      (node (ref "NL-652ETTL") (pin "3") (pinfunction "S_3") (pintype "passive"))
      (node (ref "STM32F103RET6") (pin "52") (pinfunction "PC11_52") (pintype "bidirectional"))
    )
    (net (code "77") (name "USART3_TX") (class "Default")
      (node (ref "R31") (pin "2") (pinfunction "2_2") (pintype "passive"))
      (node (ref "STM32F103RET6") (pin "51") (pinfunction "PC10_51") (pintype "bidirectional"))
    )
    (net (code "78") (name "V+") (class "Default")
      (node (ref "BAT60JFILM") (pin "A") (pinfunction "A_A") (pintype "passive"))
      (node (ref "C7") (pin "1") (pinfunction "1_1") (pintype "passive"))
      (node (ref "CH0") (pin "2") (pinfunction "2_2") (pintype "passive"))
      (node (ref "CH1") (pin "2") (pinfunction "2_2") (pintype "passive"))
      (node (ref "CH10") (pin "2") (pinfunction "2_2") (pintype "passive"))
      (node (ref "CH11") (pin "2") (pinfunction "2_2") (pintype "passive"))
      (node (ref "CH2") (pin "2") (pinfunction "2_2") (pintype "passive"))
      (node (ref "CH3") (pin "2") (pinfunction "2_2") (pintype "passive"))
      (node (ref "CH4") (pin "2") (pinfunction "2_2") (pintype "passive"))
      (node (ref "CH5") (pin "2") (pinfunction "2_2") (pintype "passive"))
      (node (ref "CH6") (pin "2") (pinfunction "2_2") (pintype "passive"))
      (node (ref "CH7") (pin "2") (pinfunction "2_2") (pintype "passive"))
      (node (ref "CH8") (pin "2") (pinfunction "2_2") (pintype "passive"))
      (node (ref "CH9") (pin "2") (pinfunction "2_2") (pintype "passive"))
    )
    (net (code "79") (name "VBAT_S") (class "Default")
      (node (ref "R29") (pin "1") (pinfunction "1_1") (pintype "passive"))
      (node (ref "R30") (pin "1") (pinfunction "1_1") (pintype "passive"))
      (node (ref "STM32F103RET6") (pin "26") (pinfunction "PB0_26") (pintype "bidirectional"))
    )
    (net (code "80") (name "VCC") (class "Default")
      (node (ref "C10") (pin "1") (pinfunction "1_1") (pintype "passive"))
      (node (ref "C12") (pin "1") (pinfunction "1_1") (pintype "passive"))
      (node (ref "C13") (pin "1") (pinfunction "1_1") (pintype "passive"))
      (node (ref "C14") (pin "1") (pinfunction "1_1") (pintype "passive"))
      (node (ref "C15") (pin "1") (pinfunction "1_1") (pintype "passive"))
      (node (ref "C17") (pin "1") (pinfunction "1_1") (pintype "passive"))
      (node (ref "C18") (pin "1") (pinfunction "1_1") (pintype "passive"))
      (node (ref "C20") (pin "1") (pinfunction "1_1") (pintype "passive"))
      (node (ref "C4") (pin "2") (pinfunction "2_2") (pintype "passive"))
      (node (ref "C6") (pin "1") (pinfunction "1_1") (pintype "passive"))
      (node (ref "FCM1608-0603") (pin "1") (pinfunction "P$1_1") (pintype "bidirectional"))
      (node (ref "HALL1") (pin "1") (pinfunction "S_1") (pintype "passive"))
      (node (ref "HALL2") (pin "1") (pinfunction "S_1") (pintype "passive"))
      (node (ref "IC1") (pin "2") (pinfunction "VOUT_2") (pintype "power_in"))
      (node (ref "IC1") (pin "4") (pinfunction "VOUT_4") (pintype "power_in"))
      (node (ref "IMU") (pin "1") (pinfunction "S_1") (pintype "passive"))
      (node (ref "I_T_V") (pin "4") (pinfunction "S_4") (pintype "passive"))
      (node (ref "MAXSONAR") (pin "2") (pinfunction "S_2") (pintype "passive"))
      (node (ref "NRF24L01+") (pin "2") (pinfunction "2_2") (pintype "passive"))
      (node (ref "R11") (pin "2") (pinfunction "2_2") (pintype "passive"))
      (node (ref "R17") (pin "1") (pinfunction "1_1") (pintype "passive"))
      (node (ref "R18") (pin "1") (pinfunction "1_1") (pintype "passive"))
      (node (ref "R20") (pin "2") (pinfunction "2_2") (pintype "passive"))
      (node (ref "R22") (pin "1") (pinfunction "1_1") (pintype "passive"))
      (node (ref "R23") (pin "1") (pinfunction "1_1") (pintype "passive"))
      (node (ref "R3") (pin "1") (pinfunction "1_1") (pintype "passive"))
      (node (ref "R9") (pin "1") (pinfunction "1_1") (pintype "passive"))
      (node (ref "STM32F103RET6") (pin "1") (pinfunction "VBAT_1") (pintype "power_in"))
      (node (ref "STM32F103RET6") (pin "19") (pinfunction "VDD_4_19") (pintype "power_in"))
      (node (ref "STM32F103RET6") (pin "32") (pinfunction "VDD_1_32") (pintype "power_in"))
      (node (ref "STM32F103RET6") (pin "48") (pinfunction "VDD_2_48") (pintype "power_in"))
      (node (ref "STM32F103RET6") (pin "64") (pinfunction "VDD_3_64") (pintype "power_in"))
      (node (ref "SWD") (pin "1") (pinfunction "S_1") (pintype "passive"))
      (node (ref "U$3") (pin "5") (pinfunction "VCC_5") (pintype "bidirectional"))
    )
    (net (code "81") (name "VDD") (class "Default")
      (node (ref "BAT60JFILM") (pin "C") (pinfunction "C_C") (pintype "passive"))
      (node (ref "IC1") (pin "3") (pinfunction "VIN_3") (pintype "input"))
      (node (ref "NL-652ETTL") (pin "1") (pinfunction "S_1") (pintype "passive"))
    )
    (net (code "82") (name "unconnected-(STM32F103RET6B-PA11-Pad44)") (class "Default")
      (node (ref "STM32F103RET6") (pin "44") (pinfunction "PA11_44") (pintype "bidirectional"))
    )
    (net (code "83") (name "unconnected-(STM32F103RET6B-PA15-Pad50)") (class "Default")
      (node (ref "STM32F103RET6") (pin "50") (pinfunction "PA15_50") (pintype "bidirectional"))
    )
    (net (code "84") (name "unconnected-(STM32F103RET6F-PC13-Pad2)") (class "Default")
      (node (ref "STM32F103RET6") (pin "2") (pinfunction "PC13_2") (pintype "bidirectional"))
    )
    (net (code "85") (name "unconnected-(STM32F103RET6F-PC14-Pad3)") (class "Default")
      (node (ref "STM32F103RET6") (pin "3") (pinfunction "PC14_3") (pintype "bidirectional"))
    )
    (net (code "86") (name "unconnected-(STM32F103RET6F-PC15-Pad4)") (class "Default")
      (node (ref "STM32F103RET6") (pin "4") (pinfunction "PC15_4") (pintype "bidirectional"))
    )
    (net (code "87") (name "unconnected-(STM32F103RET6G-PC0-Pad8)") (class "Default")
      (node (ref "STM32F103RET6") (pin "8") (pinfunction "PC0_8") (pintype "bidirectional"))
    )
    (net (code "88") (name "unconnected-(STM32F103RET6G-PC3-Pad11)") (class "Default")
      (node (ref "STM32F103RET6") (pin "11") (pinfunction "PC3_11") (pintype "bidirectional"))
    )
    (net (code "89") (name "unconnected-(STM32F103RET6G-PC5-Pad25)") (class "Default")
      (node (ref "STM32F103RET6") (pin "25") (pinfunction "PC5_25") (pintype "bidirectional"))
    )
    (net (code "90") (name "unconnected-(STM32F103RET6H-PD2-Pad54)") (class "Default")
      (node (ref "STM32F103RET6") (pin "54") (pinfunction "PD2_54") (pintype "bidirectional"))
    )
    (net (code "91") (name "unconnected-(U$3-GPIO2-Pad8)") (class "Default")
      (node (ref "U$3") (pin "8") (pinfunction "GPIO2_8") (pintype "bidirectional"))
    )
  )
)
